# ESP32-SolorCharge.net
KiCad netlist of a schematic drawn in EAGLE
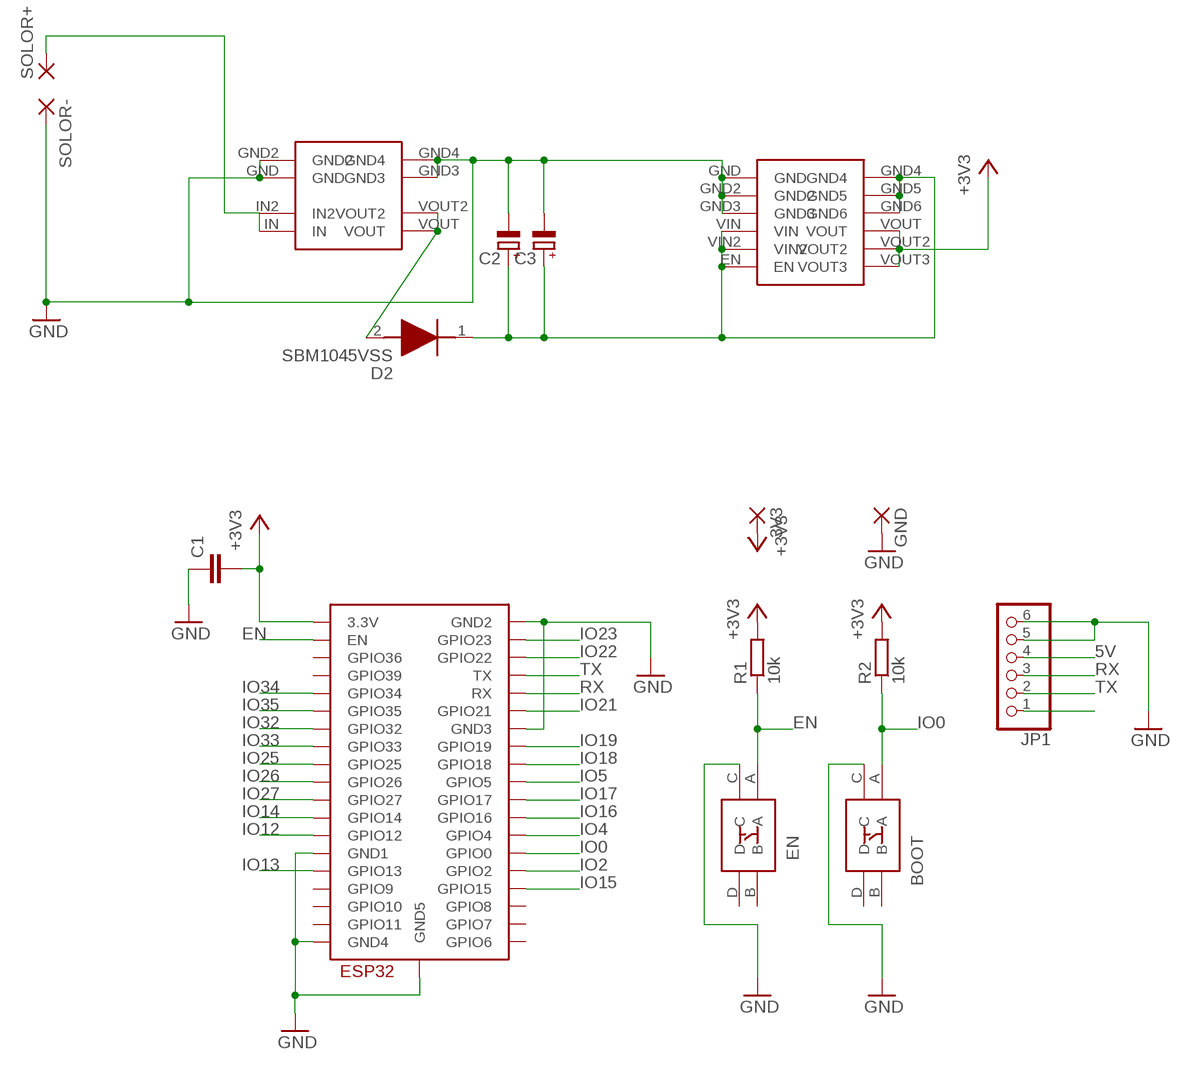
[diagram p0: schematic, sheet 1]

(export (version "E")
  (design (tool "Eeschema 10.0.6"))
  (components
    (comp (ref "3V3")
      (value "2,54/1,0")
      (footprint "eagle-import:2,54_1,0")
      (libsource (lib "eagle-import") (part "2,54/1,0"))
    )
    (comp (ref "BOOT")
      (value "TS-06104")
      (footprint "eagle-import:TS06104")
      (libsource (lib "eagle-import") (part "TS-06104"))
    )
    (comp (ref "C1")
      (value "C-EU025-025X050")
      (footprint "eagle-import:C025-025X050")
      (libsource (lib "eagle-import") (part "C-EU025-025X050"))
    )
    (comp (ref "C2")
      (value "CPOL-EUE7.5-16")
      (footprint "eagle-import:E7,5-16")
      (libsource (lib "eagle-import") (part "CPOL-EUE7.5-16"))
    )
    (comp (ref "C3")
      (value "CPOL-EUE7.5-16")
      (footprint "eagle-import:E7,5-16")
      (libsource (lib "eagle-import") (part "CPOL-EUE7.5-16"))
    )
    (comp (ref "D2")
      (value "SBM1045VSS")
      (footprint "eagle-import:DIOAD2855W130L835D505")
      (libsource (lib "eagle-import") (part "SBM1045VSS"))
    )
    (comp (ref "EN")
      (value "TS-06104")
      (footprint "eagle-import:TS06104")
      (libsource (lib "eagle-import") (part "TS-06104"))
    )
    (comp (ref "GND")
      (value "2,54/1,0")
      (footprint "eagle-import:2,54_1,0")
      (libsource (lib "eagle-import") (part "2,54/1,0"))
    )
    (comp (ref "JP1")
      (value "PINHD-1X6")
      (footprint "eagle-import:1X06")
      (libsource (lib "eagle-import") (part "PINHD-1X6"))
    )
    (comp (ref "R1")
      (value "10k")
      (footprint "eagle-import:R0603")
      (libsource (lib "eagle-import") (part "R-EU_R0603"))
    )
    (comp (ref "R2")
      (value "10k")
      (footprint "eagle-import:R0603")
      (libsource (lib "eagle-import") (part "R-EU_R0603"))
    )
    (comp (ref "SOLOR+")
      (value "2,54/1,0")
      (footprint "eagle-import:2,54_1,0")
      (libsource (lib "eagle-import") (part "2,54/1,0"))
    )
    (comp (ref "SOLOR-")
      (value "2,54/1,0")
      (footprint "eagle-import:2,54_1,0")
      (libsource (lib "eagle-import") (part "2,54/1,0"))
    )
    (comp (ref "U$1")
      (value "ESP32-WROOM")
      (footprint "eagle-import:ESP32-WROOM")
      (libsource (lib "eagle-import") (part "ESP32-WROOM"))
    )
    (comp (ref "U$2")
      (value "TPS63070")
      (footprint "eagle-import:TPS63070")
      (libsource (lib "eagle-import") (part "TPS63070"))
    )
    (comp (ref "U$3")
      (value "TPS63020")
      (footprint "eagle-import:TPS63020")
      (libsource (lib "eagle-import") (part "TPS63020"))
    )
  )
  (nets
    (net (code "1") (name "+3V3") (class "Default")
      (node (ref "3V3") (pin "1") (pinfunction "P_1") (pintype "passive"))
      (node (ref "C1") (pin "2") (pinfunction "2_2") (pintype "passive"))
      (node (ref "R1") (pin "2") (pinfunction "2_2") (pintype "passive"))
      (node (ref "R2") (pin "2") (pinfunction "2_2") (pintype "passive"))
      (node (ref "U$1") (pin "3V3") (pinfunction "3.3V_3V3") (pintype "bidirectional"))
      (node (ref "U$3") (pin "VOUT") (pinfunction "VOUT_VOUT") (pintype "bidirectional"))
      (node (ref "U$3") (pin "VOUT2") (pinfunction "VOUT2_VOUT2") (pintype "bidirectional"))
      (node (ref "U$3") (pin "VOUT3") (pinfunction "VOUT3_VOUT3") (pintype "bidirectional"))
    )
    (net (code "2") (name "/5V") (class "Default")
      (node (ref "JP1") (pin "4") (pinfunction "4_4") (pintype "passive"))
    )
    (net (code "3") (name "/EN") (class "Default")
      (node (ref "EN") (pin "A") (pinfunction "A_A") (pintype "bidirectional"))
      (node (ref "R1") (pin "1") (pinfunction "1_1") (pintype "passive"))
      (node (ref "U$1") (pin "EN") (pinfunction "EN_EN") (pintype "bidirectional"))
    )
    (net (code "4") (name "/IO0") (class "Default")
      (node (ref "BOOT") (pin "A") (pinfunction "A_A") (pintype "bidirectional"))
      (node (ref "R2") (pin "1") (pinfunction "1_1") (pintype "passive"))
      (node (ref "U$1") (pin "IO0") (pinfunction "GPIO0_IO0") (pintype "bidirectional"))
    )
    (net (code "5") (name "/IO2") (class "Default")
      (node (ref "U$1") (pin "IO2") (pinfunction "GPIO2_IO2") (pintype "bidirectional"))
    )
    (net (code "6") (name "/IO4") (class "Default")
      (node (ref "U$1") (pin "IO4") (pinfunction "GPIO4_IO4") (pintype "bidirectional"))
    )
    (net (code "7") (name "/IO5") (class "Default")
      (node (ref "U$1") (pin "IO5") (pinfunction "GPIO5_IO5") (pintype "bidirectional"))
    )
    (net (code "8") (name "/IO12") (class "Default")
      (node (ref "U$1") (pin "IO12") (pinfunction "GPIO12_IO12") (pintype "bidirectional"))
    )
    (net (code "9") (name "/IO13") (class "Default")
      (node (ref "U$1") (pin "IO13") (pinfunction "GPIO13_IO13") (pintype "bidirectional"))
    )
    (net (code "10") (name "/IO14") (class "Default")
      (node (ref "U$1") (pin "IO14") (pinfunction "GPIO14_IO14") (pintype "bidirectional"))
    )
    (net (code "11") (name "/IO15") (class "Default")
      (node (ref "U$1") (pin "IO15") (pinfunction "GPIO15_IO15") (pintype "bidirectional"))
    )
    (net (code "12") (name "/IO16") (class "Default")
      (node (ref "U$1") (pin "IO16") (pinfunction "GPIO16_IO16") (pintype "bidirectional"))
    )
    (net (code "13") (name "/IO17") (class "Default")
      (node (ref "U$1") (pin "IO17") (pinfunction "GPIO17_IO17") (pintype "bidirectional"))
    )
    (net (code "14") (name "/IO18") (class "Default")
      (node (ref "U$1") (pin "IO18") (pinfunction "GPIO18_IO18") (pintype "bidirectional"))
    )
    (net (code "15") (name "/IO19") (class "Default")
      (node (ref "U$1") (pin "IO19") (pinfunction "GPIO19_IO19") (pintype "bidirectional"))
    )
    (net (code "16") (name "/IO21") (class "Default")
      (node (ref "U$1") (pin "IO21") (pinfunction "GPIO21_IO21") (pintype "bidirectional"))
    )
    (net (code "17") (name "/IO22") (class "Default")
      (node (ref "U$1") (pin "IO22") (pinfunction "GPIO22_IO22") (pintype "bidirectional"))
    )
    (net (code "18") (name "/IO23") (class "Default")
      (node (ref "U$1") (pin "IO23") (pinfunction "GPIO23_IO23") (pintype "bidirectional"))
    )
    (net (code "19") (name "/IO25") (class "Default")
      (node (ref "U$1") (pin "IO25") (pinfunction "GPIO25_IO25") (pintype "bidirectional"))
    )
    (net (code "20") (name "/IO26") (class "Default")
      (node (ref "U$1") (pin "IO26") (pinfunction "GPIO26_IO26") (pintype "bidirectional"))
    )
    (net (code "21") (name "/IO27") (class "Default")
      (node (ref "U$1") (pin "IO27") (pinfunction "GPIO27_IO27") (pintype "bidirectional"))
    )
    (net (code "22") (name "/IO32") (class "Default")
      (node (ref "U$1") (pin "IO32") (pinfunction "GPIO32_IO32") (pintype "bidirectional"))
    )
    (net (code "23") (name "/IO33") (class "Default")
      (node (ref "U$1") (pin "IO33") (pinfunction "GPIO33_IO33") (pintype "bidirectional"))
    )
    (net (code "24") (name "/IO34") (class "Default")
      (node (ref "U$1") (pin "IO34") (pinfunction "GPIO34_IO34") (pintype "bidirectional"))
    )
    (net (code "25") (name "/IO35") (class "Default")
      (node (ref "U$1") (pin "IO35") (pinfunction "GPIO35_IO35") (pintype "bidirectional"))
    )
    (net (code "26") (name "/RX") (class "Default")
      (node (ref "JP1") (pin "3") (pinfunction "3_3") (pintype "passive"))
      (node (ref "U$1") (pin "RX") (pinfunction "RX_RX") (pintype "bidirectional"))
    )
    (net (code "27") (name "/TX") (class "Default")
      (node (ref "JP1") (pin "2") (pinfunction "2_2") (pintype "passive"))
      (node (ref "U$1") (pin "TX") (pinfunction "TX_TX") (pintype "bidirectional"))
    )
    (net (code "28") (name "GND") (class "Default")
      (node (ref "BOOT") (pin "C") (pinfunction "C_C") (pintype "bidirectional"))
      (node (ref "C1") (pin "1") (pinfunction "1_1") (pintype "passive"))
      (node (ref "C2") (pin "-") (pinfunction "-_-") (pintype "passive"))
      (node (ref "C3") (pin "-") (pinfunction "-_-") (pintype "passive"))
      (node (ref "EN") (pin "C") (pinfunction "C_C") (pintype "bidirectional"))
      (node (ref "GND") (pin "1") (pinfunction "P_1") (pintype "passive"))
      (node (ref "JP1") (pin "5") (pinfunction "5_5") (pintype "passive"))
      (node (ref "JP1") (pin "6") (pinfunction "6_6") (pintype "passive"))
      (node (ref "SOLOR-") (pin "1") (pinfunction "P_1") (pintype "passive"))
      (node (ref "U$1") (pin "GND1") (pinfunction "GND1_GND1") (pintype "bidirectional"))
      (node (ref "U$1") (pin "GND2") (pinfunction "GND2_GND2") (pintype "bidirectional"))
      (node (ref "U$1") (pin "GND3") (pinfunction "GND3_GND3") (pintype "bidirectional"))
      (node (ref "U$1") (pin "GND4") (pinfunction "GND4_GND4") (pintype "bidirectional"))
      (node (ref "U$1") (pin "GND5") (pinfunction "GND5_GND5") (pintype "bidirectional"))
      (node (ref "U$2") (pin "GND") (pinfunction "GND_GND") (pintype "bidirectional"))
      (node (ref "U$2") (pin "GND2") (pinfunction "GND2_GND2") (pintype "bidirectional"))
      (node (ref "U$2") (pin "GND3") (pinfunction "GND3_GND3") (pintype "bidirectional"))
      (node (ref "U$2") (pin "GND4") (pinfunction "GND4_GND4") (pintype "bidirectional"))
      (node (ref "U$3") (pin "GND") (pinfunction "GND_GND") (pintype "bidirectional"))
      (node (ref "U$3") (pin "GND2") (pinfunction "GND2_GND2") (pintype "bidirectional"))
      (node (ref "U$3") (pin "GND3") (pinfunction "GND3_GND3") (pintype "bidirectional"))
    )
    (net (code "29") (name "Net-(D2-A)") (class "Default")
      (node (ref "D2") (pin "2") (pinfunction "A_2") (pintype "bidirectional"))
      (node (ref "U$2") (pin "VOUT") (pinfunction "VOUT_VOUT") (pintype "bidirectional"))
      (node (ref "U$2") (pin "VOUT2") (pinfunction "VOUT2_VOUT2") (pintype "bidirectional"))
    )
    (net (code "30") (name "Net-(D2-K)") (class "Default")
      (node (ref "C2") (pin "+") (pinfunction "+_+") (pintype "passive"))
      (node (ref "C3") (pin "+") (pinfunction "+_+") (pintype "passive"))
      (node (ref "D2") (pin "1") (pinfunction "K_1") (pintype "bidirectional"))
      (node (ref "U$3") (pin "EN") (pinfunction "EN_EN") (pintype "bidirectional"))
      (node (ref "U$3") (pin "GND4") (pinfunction "GND4_GND4") (pintype "bidirectional"))
      (node (ref "U$3") (pin "GND5") (pinfunction "GND5_GND5") (pintype "bidirectional"))
      (node (ref "U$3") (pin "GND6") (pinfunction "GND6_GND6") (pintype "bidirectional"))
      (node (ref "U$3") (pin "VIN") (pinfunction "VIN_VIN") (pintype "bidirectional"))
      (node (ref "U$3") (pin "VIN2") (pinfunction "VIN2_VIN2") (pintype "bidirectional"))
    )
    (net (code "31") (name "Net-(SOLOR+-P)") (class "Default")
      (node (ref "SOLOR+") (pin "1") (pinfunction "P_1") (pintype "passive"))
      (node (ref "U$2") (pin "IN") (pinfunction "IN_IN") (pintype "bidirectional"))
      (node (ref "U$2") (pin "IN2") (pinfunction "IN2_IN2") (pintype "bidirectional"))
    )
    (net (code "32") (name "unconnected-(BOOT-PadB)") (class "Default")
      (node (ref "BOOT") (pin "B") (pinfunction "B_B") (pintype "bidirectional"))
    )
    (net (code "33") (name "unconnected-(BOOT-PadD)") (class "Default")
      (node (ref "BOOT") (pin "D") (pinfunction "D_D") (pintype "bidirectional"))
    )
    (net (code "34") (name "unconnected-(EN-PadB)") (class "Default")
      (node (ref "EN") (pin "B") (pinfunction "B_B") (pintype "bidirectional"))
    )
    (net (code "35") (name "unconnected-(EN-PadD)") (class "Default")
      (node (ref "EN") (pin "D") (pinfunction "D_D") (pintype "bidirectional"))
    )
    (net (code "36") (name "unconnected-(JP1-Pad1)") (class "Default")
      (node (ref "JP1") (pin "1") (pinfunction "1_1") (pintype "passive"))
    )
    (net (code "37") (name "unconnected-(U$1-GPIO6-PadCLK)") (class "Default")
      (node (ref "U$1") (pin "CLK") (pinfunction "GPIO6_CLK") (pintype "bidirectional"))
    )
    (net (code "38") (name "unconnected-(U$1-GPIO7-PadSD0)") (class "Default")
      (node (ref "U$1") (pin "SD0") (pinfunction "GPIO7_SD0") (pintype "bidirectional"))
    )
    (net (code "39") (name "unconnected-(U$1-GPIO8-PadSD1)") (class "Default")
      (node (ref "U$1") (pin "SD1") (pinfunction "GPIO8_SD1") (pintype "bidirectional"))
    )
    (net (code "40") (name "unconnected-(U$1-GPIO9-PadSD2)") (class "Default")
      (node (ref "U$1") (pin "SD2") (pinfunction "GPIO9_SD2") (pintype "bidirectional"))
    )
    (net (code "41") (name "unconnected-(U$1-GPIO10-PadSD3)") (class "Default")
      (node (ref "U$1") (pin "SD3") (pinfunction "GPIO10_SD3") (pintype "bidirectional"))
    )
    (net (code "42") (name "unconnected-(U$1-GPIO11-PadCMD)") (class "Default")
      (node (ref "U$1") (pin "CMD") (pinfunction "GPIO11_CMD") (pintype "bidirectional"))
    )
    (net (code "43") (name "unconnected-(U$1-GPIO36-PadSENSOR_VP)") (class "Default")
      (node (ref "U$1") (pin "SENSOR_VP") (pinfunction "GPIO36_SENSOR_VP") (pintype "bidirectional"))
    )
    (net (code "44") (name "unconnected-(U$1-GPIO39-PadSENSOR_VN)") (class "Default")
      (node (ref "U$1") (pin "SENSOR_VN") (pinfunction "GPIO39_SENSOR_VN") (pintype "bidirectional"))
    )
  )
)
